# Headphone-Amplifier-ClassAB-alt2.net
KiCad netlist of a schematic drawn in EAGLE
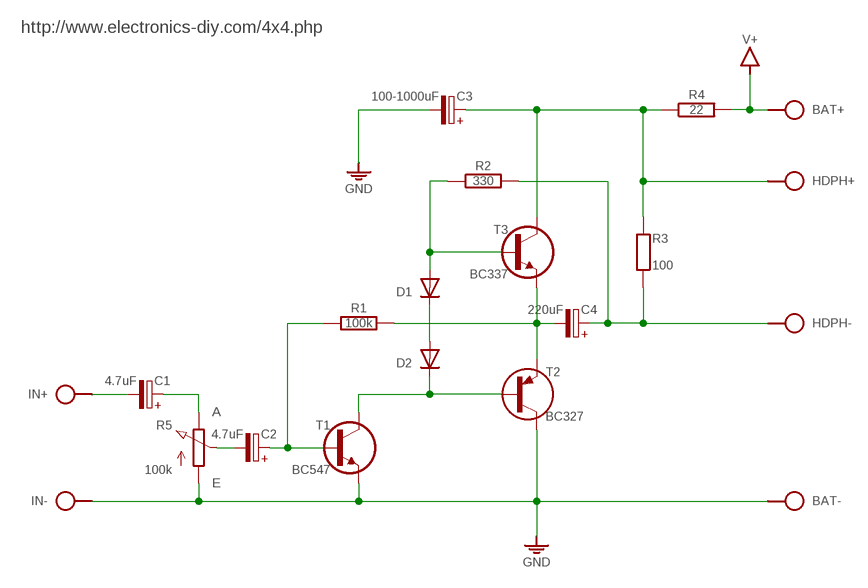
[diagram p0: schematic, sheet 1]

(export (version "E")
  (design (tool "Eeschema 10.0.6"))
  (components
    (comp (ref "BAT")
      (value "SPAD+-+-")
      (footprint "eagle-import:SPAD+-")
      (libsource (lib "eagle-import") (part "SPAD+-+-"))
    )
    (comp (ref "C1")
      (value "4.7uF")
      (footprint "eagle-import:E2,5-4")
      (libsource (lib "eagle-import") (part "CPOL-HE2,5-4"))
    )
    (comp (ref "C2")
      (value "4.7uF")
      (footprint "eagle-import:E2,5-4")
      (libsource (lib "eagle-import") (part "CPOL-HE2,5-4"))
    )
    (comp (ref "C3")
      (value "100-1000uF")
      (footprint "eagle-import:E2,5-6_V")
      (libsource (lib "eagle-import") (part "CPOL-HE2,5-6/V"))
    )
    (comp (ref "C4")
      (value "220uF")
      (footprint "eagle-import:E2,5-5")
      (libsource (lib "eagle-import") (part "CPOL-HE2,5-5"))
    )
    (comp (ref "D1")
      (value "DIODE34-5V")
      (footprint "eagle-import:DO34-5V")
      (libsource (lib "eagle-import") (part "DIODE34-5V"))
    )
    (comp (ref "D2")
      (value "DIODE34-5V")
      (footprint "eagle-import:DO34-5V")
      (libsource (lib "eagle-import") (part "DIODE34-5V"))
    )
    (comp (ref "HDPH")
      (value "SPAD+--+")
      (footprint "eagle-import:SPAD-+")
      (libsource (lib "eagle-import") (part "SPAD+--+"))
    )
    (comp (ref "IN")
      (value "SPAD+--+")
      (footprint "eagle-import:SPAD-+")
      (libsource (lib "eagle-import") (part "SPAD+--+"))
    )
    (comp (ref "R1")
      (value "100k")
      (footprint "eagle-import:0202_5")
      (libsource (lib "eagle-import") (part "R-H0202/5"))
    )
    (comp (ref "R2")
      (value "330")
      (footprint "eagle-import:0204_10")
      (libsource (lib "eagle-import") (part "R-H0204/10"))
    )
    (comp (ref "R3")
      (value "100")
      (footprint "eagle-import:0204_10")
      (libsource (lib "eagle-import") (part "R0204/10"))
    )
    (comp (ref "R4")
      (value "22")
      (footprint "eagle-import:0204_2.54")
      (libsource (lib "eagle-import") (part "R-H0204/2.54"))
    )
    (comp (ref "R5")
      (value "100k")
      (footprint "eagle-import:CONN-3P")
      (libsource (lib "eagle-import") (part "POT-3P"))
    )
    (comp (ref "T1")
      (value "BC547")
      (footprint "eagle-import:TO92-CBE")
      (libsource (lib "eagle-import") (part "BC547CBE"))
    )
    (comp (ref "T2")
      (value "BC327")
      (footprint "eagle-import:TO92")
      (libsource (lib "eagle-import") (part "BC327"))
    )
    (comp (ref "T3")
      (value "BC337")
      (footprint "eagle-import:TO92-CBE")
      (libsource (lib "eagle-import") (part "BC337CBE"))
    )
  )
  (nets
    (net (code "1") (name "GND") (class "Default")
      (node (ref "BAT") (pin "1") (pinfunction "P$1_1") (pintype "passive"))
      (node (ref "C3") (pin "-") (pinfunction "-_-") (pintype "passive"))
      (node (ref "IN") (pin "1") (pinfunction "P$1_1") (pintype "passive"))
      (node (ref "R5") (pin "1") (pinfunction "A_1") (pintype "passive"))
      (node (ref "T1") (pin "E") (pinfunction "E_E") (pintype "passive"))
      (node (ref "T2") (pin "1") (pinfunction "C_1") (pintype "passive"))
    )
    (net (code "2") (name "Net-(C2-Pad+)") (class "Default")
      (node (ref "C2") (pin "+") (pinfunction "+_+") (pintype "passive"))
      (node (ref "R1") (pin "1") (pinfunction "1_1") (pintype "passive"))
      (node (ref "T1") (pin "B") (pinfunction "B_B") (pintype "passive"))
    )
    (net (code "3") (name "Net-(D1-PadA)") (class "Default")
      (node (ref "D1") (pin "A") (pinfunction "A_A") (pintype "passive"))
      (node (ref "R2") (pin "1") (pinfunction "1_1") (pintype "passive"))
      (node (ref "T3") (pin "B") (pinfunction "B_B") (pintype "passive"))
    )
    (net (code "4") (name "Net-(D1-PadC)") (class "Default")
      (node (ref "D1") (pin "C") (pinfunction "C_C") (pintype "passive"))
      (node (ref "D2") (pin "A") (pinfunction "A_A") (pintype "passive"))
    )
    (net (code "5") (name "Net-(HDPHA-P$1)") (class "Default")
      (node (ref "C3") (pin "+") (pinfunction "+_+") (pintype "passive"))
      (node (ref "HDPH") (pin "2") (pinfunction "P$1_2") (pintype "passive"))
      (node (ref "R3") (pin "1") (pinfunction "1_1") (pintype "passive"))
      (node (ref "R4") (pin "1") (pinfunction "1_1") (pintype "passive"))
      (node (ref "T3") (pin "C") (pinfunction "C_C") (pintype "passive"))
    )
    (net (code "6") (name "Net-(HDPHB-P$1)") (class "Default")
      (node (ref "C4") (pin "+") (pinfunction "+_+") (pintype "passive"))
      (node (ref "HDPH") (pin "1") (pinfunction "P$1_1") (pintype "passive"))
      (node (ref "R2") (pin "2") (pinfunction "2_2") (pintype "passive"))
      (node (ref "R3") (pin "2") (pinfunction "2_2") (pintype "passive"))
    )
    (net (code "7") (name "Net-(INA-P$1)") (class "Default")
      (node (ref "C1") (pin "-") (pinfunction "-_-") (pintype "passive"))
      (node (ref "IN") (pin "2") (pinfunction "P$1_2") (pintype "passive"))
    )
    (net (code "8") (name "Net-(R5-E)") (class "Default")
      (node (ref "C1") (pin "+") (pinfunction "+_+") (pintype "passive"))
      (node (ref "R5") (pin "3") (pinfunction "E_3") (pintype "passive"))
    )
    (net (code "9") (name "Net-(R5-S)") (class "Default")
      (node (ref "C2") (pin "-") (pinfunction "-_-") (pintype "passive"))
      (node (ref "R5") (pin "2") (pinfunction "S_2") (pintype "passive"))
    )
    (net (code "10") (name "Net-(T2-B)") (class "Default")
      (node (ref "D2") (pin "C") (pinfunction "C_C") (pintype "passive"))
      (node (ref "T1") (pin "C") (pinfunction "C_C") (pintype "passive"))
      (node (ref "T2") (pin "2") (pinfunction "B_2") (pintype "passive"))
    )
    (net (code "11") (name "Net-(T2-E)") (class "Default")
      (node (ref "C4") (pin "-") (pinfunction "-_-") (pintype "passive"))
      (node (ref "R1") (pin "2") (pinfunction "2_2") (pintype "passive"))
      (node (ref "T2") (pin "3") (pinfunction "E_3") (pintype "passive"))
      (node (ref "T3") (pin "E") (pinfunction "E_E") (pintype "passive"))
    )
    (net (code "12") (name "V+") (class "Default")
      (node (ref "BAT") (pin "2") (pinfunction "P$1_2") (pintype "passive"))
      (node (ref "R4") (pin "2") (pinfunction "2_2") (pintype "passive"))
    )
  )
)
